# ADC.net
KiCad netlist of a schematic drawn in Altium Designer
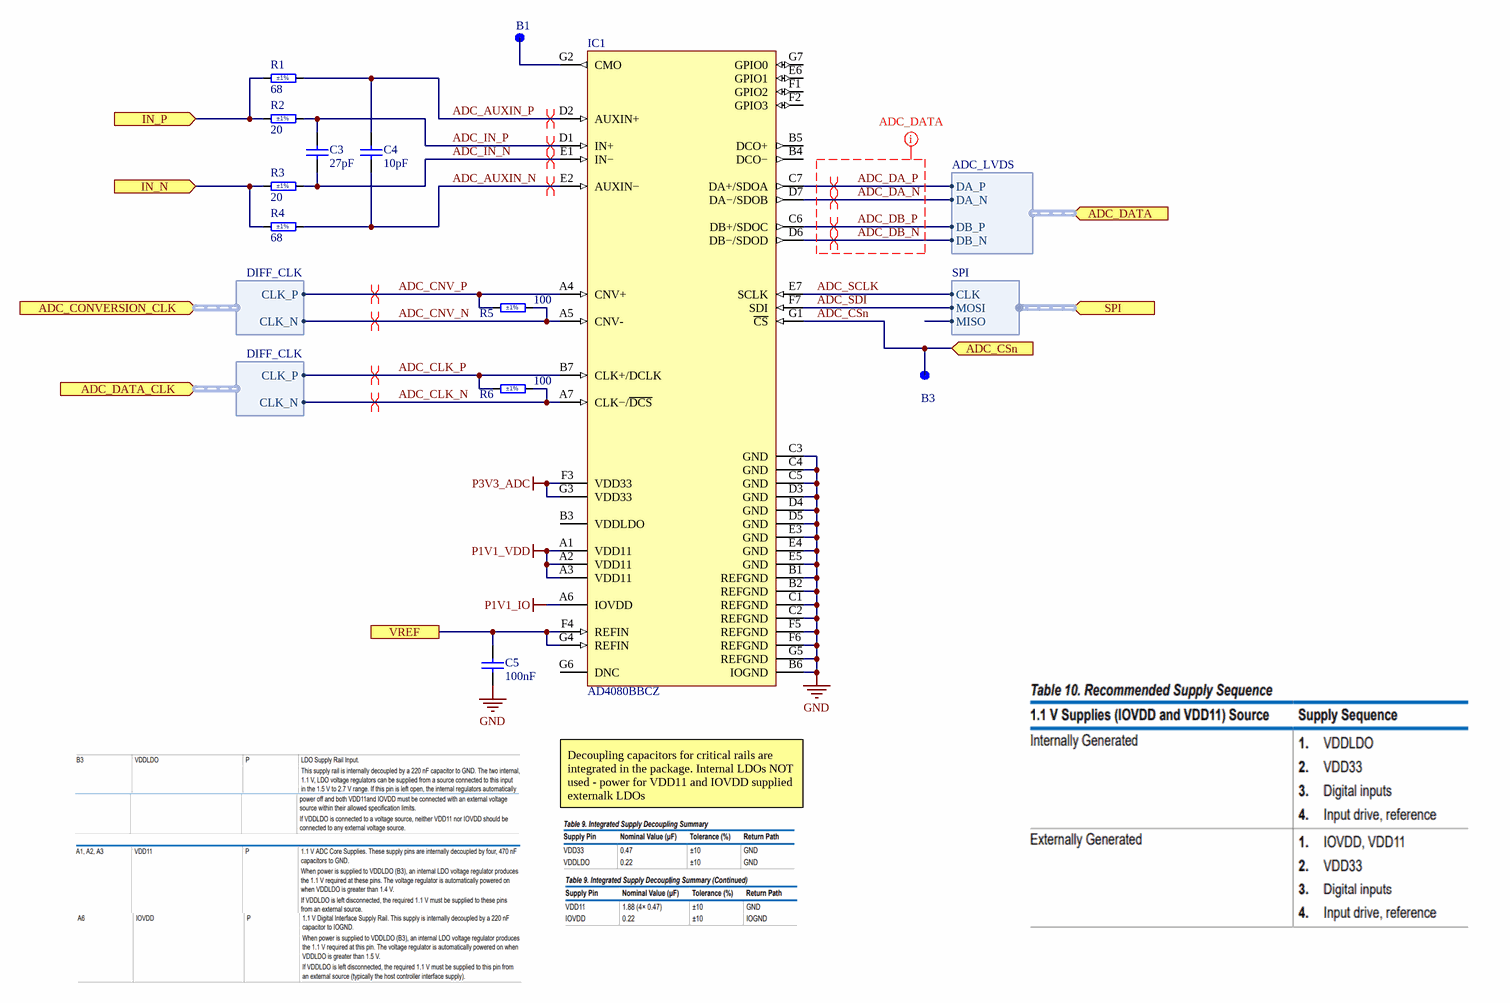
[diagram p0: ADC.SchDoc]

(export (version "E")
  (design (tool "Eeschema 10.0.6"))
  (components
    (comp (ref "B1")
      (value "SMD Pad")
      (footprint "C100")
      (description "Pad")
      (fields (field (name "PART NUMBER") "SMD_PAD_D1MM") (field (name "AUTHOR") "CERN DEM JLC"))
      (libsource (lib "Eletro-mechanical") (part "Single SMD Pad (Round)"))
    )
    (comp (ref "B3")
      (value "SMD Pad")
      (footprint "C100")
      (description "Pad")
      (fields (field (name "PART NUMBER") "SMD_PAD_D1MM") (field (name "AUTHOR") "CERN DEM JLC"))
      (libsource (lib "Eletro-mechanical") (part "Single SMD Pad (Round)"))
    )
    (comp (ref "C3")
      (value "27pF")
      (footprint "CAPC1005X55N")
      (description "Non-polarised capacitor")
      (fields
        (field (name "PART NUMBER") "CC0402_27PF_50V_5%_C0G")
        (field (name "VOLTAGE") "50V")
        (field (name "AUTHOR") "CERN DEM JLC")
      )
      (libsource (lib "Capacitors") (part "Capacitor - non polarized"))
    )
    (comp (ref "C4")
      (value "10pF")
      (footprint "CAPC1005X55N")
      (description "Non-polarised capacitor")
      (fields
        (field (name "PART NUMBER") "CC0402_10PF_50V_5%_C0G")
        (field (name "VOLTAGE") "50V")
        (field (name "AUTHOR") "CERN DEM JLC")
      )
      (libsource (lib "Capacitors") (part "Capacitor - non polarized"))
    )
    (comp (ref "C5")
      (value "100nF")
      (footprint "CAPC1005X55N")
      (description "Non-polarised capacitor")
      (fields
        (field (name "PART NUMBER") "CC0402_100NF_50V_10%_X7R")
        (field (name "VOLTAGE") "50V")
        (field (name "AUTHOR") "CERN DEM MR")
      )
      (libsource (lib "Capacitors") (part "Capacitor - non polarized"))
    )
    (comp (ref "IC1")
      (value "AD4080BBCZ")
      (footprint "BGA49C65P7X7_500X500X138")
      (description "20-Bit, 40 MSPS, Differential SAR ADC")
      (fields (field (name "MANUFACTURER") "Analog Devices") (field (name "AUTHOR") "Michal Beldyga"))
      (libsource (lib "Semiconductors") (part "AD4080"))
    )
    (comp (ref "R1")
      (value "68")
      (footprint "RESC1005X40N")
      (description "Resistor - 1%")
      (fields
        (field (name "TOLERANCE") "±1%")
        (field (name "PART NUMBER") "R0402_68R_1%_0.0625W_100PPM")
        (field (name "POWER") "0.0625W")
        (field (name "AUTHOR") "CERN DEM JLC")
      )
      (libsource (lib "Resistors") (part "Resistor - 1%"))
    )
    (comp (ref "R2")
      (value "20")
      (footprint "RESC1005X40N")
      (description "Resistor - 1%")
      (fields
        (field (name "TOLERANCE") "±1%")
        (field (name "PART NUMBER") "R0402_20R_1%_0.0625W_100PPM")
        (field (name "POWER") "0.0625W")
        (field (name "AUTHOR") "CERN DEM JLC")
      )
      (libsource (lib "Resistors") (part "Resistor - 1%"))
    )
    (comp (ref "R3")
      (value "20")
      (footprint "RESC1005X40N")
      (description "Resistor - 1%")
      (fields
        (field (name "TOLERANCE") "±1%")
        (field (name "PART NUMBER") "R0402_20R_1%_0.0625W_100PPM")
        (field (name "POWER") "0.0625W")
        (field (name "AUTHOR") "CERN DEM JLC")
      )
      (libsource (lib "Resistors") (part "Resistor - 1%"))
    )
    (comp (ref "R4")
      (value "68")
      (footprint "RESC1005X40N")
      (description "Resistor - 1%")
      (fields
        (field (name "TOLERANCE") "±1%")
        (field (name "PART NUMBER") "R0402_68R_1%_0.0625W_100PPM")
        (field (name "POWER") "0.0625W")
        (field (name "AUTHOR") "CERN DEM JLC")
      )
      (libsource (lib "Resistors") (part "Resistor - 1%"))
    )
    (comp (ref "R5")
      (value "100")
      (footprint "RESC1005X40N")
      (description "Resistor - 1%")
      (fields
        (field (name "TOLERANCE") "±1%")
        (field (name "PART NUMBER") "R0402_100R_1%_0.1W_100PPM")
        (field (name "POWER") "0.1W")
        (field (name "AUTHOR") "CERN DEM JLC")
      )
      (libsource (lib "Resistors") (part "Resistor - 1%"))
    )
    (comp (ref "R6")
      (value "100")
      (footprint "RESC1005X40N")
      (description "Resistor - 1%")
      (fields
        (field (name "TOLERANCE") "±1%")
        (field (name "PART NUMBER") "R0402_100R_1%_0.1W_100PPM")
        (field (name "POWER") "0.1W")
        (field (name "AUTHOR") "CERN DEM JLC")
      )
      (libsource (lib "Resistors") (part "Resistor - 1%"))
    )
  )
  (nets
    (net (code "4") (name "/ADC_AUXIN_N") (class "Default")
      (node (ref "C4") (pin "1") (pinfunction "1_1") (pintype "passive"))
      (node (ref "IC1") (pin "E2") (pinfunction "AUXIN−_E2") (pintype "input"))
      (node (ref "R4") (pin "2") (pinfunction "2_2") (pintype "passive"))
    )
    (net (code "5") (name "/ADC_AUXIN_P") (class "Default")
      (node (ref "C4") (pin "2") (pinfunction "2_2") (pintype "passive"))
      (node (ref "IC1") (pin "D2") (pinfunction "AUXIN+_D2") (pintype "input"))
      (node (ref "R1") (pin "2") (pinfunction "2_2") (pintype "passive"))
    )
    (net (code "6") (name "/ADC_CLK_N") (class "Default")
      (node (ref "IC1") (pin "A7") (pinfunction "CLK−/~{DCS}_A7") (pintype "input"))
      (node (ref "R6") (pin "2") (pinfunction "2_2") (pintype "passive"))
    )
    (net (code "7") (name "/ADC_CLK_P") (class "Default")
      (node (ref "IC1") (pin "B7") (pinfunction "CLK+/DCLK_B7") (pintype "input"))
      (node (ref "R6") (pin "1") (pinfunction "1_1") (pintype "passive"))
    )
    (net (code "8") (name "/ADC_CNV_N") (class "Default")
      (node (ref "IC1") (pin "A5") (pinfunction "CNV-_A5") (pintype "input"))
      (node (ref "R5") (pin "2") (pinfunction "2_2") (pintype "passive"))
    )
    (net (code "9") (name "/ADC_CNV_P") (class "Default")
      (node (ref "IC1") (pin "A4") (pinfunction "CNV+_A4") (pintype "input"))
      (node (ref "R5") (pin "1") (pinfunction "1_1") (pintype "passive"))
    )
    (net (code "10") (name "/ADC_CSn") (class "Default")
      (node (ref "B3") (pin "1") (pinfunction "1_1") (pintype "bidirectional"))
      (node (ref "IC1") (pin "G1") (pinfunction "~{CS}_G1") (pintype "input"))
    )
    (net (code "11") (name "/ADC_DA_N") (class "Default")
      (node (ref "IC1") (pin "D7") (pinfunction "DA−/SDOB_D7") (pintype "output"))
    )
    (net (code "12") (name "/ADC_DA_P") (class "Default")
      (node (ref "IC1") (pin "C7") (pinfunction "DA+/SDOA_C7") (pintype "output"))
    )
    (net (code "13") (name "/ADC_DB_N") (class "Default")
      (node (ref "IC1") (pin "D6") (pinfunction "DB−/SDOD_D6") (pintype "output"))
    )
    (net (code "14") (name "/ADC_DB_P") (class "Default")
      (node (ref "IC1") (pin "C6") (pinfunction "DB+/SDOC_C6") (pintype "output"))
    )
    (net (code "15") (name "/ADC_IN_N") (class "Default")
      (node (ref "C3") (pin "1") (pinfunction "1_1") (pintype "passive"))
      (node (ref "IC1") (pin "E1") (pinfunction "IN−_E1") (pintype "input"))
      (node (ref "R3") (pin "2") (pinfunction "2_2") (pintype "passive"))
    )
    (net (code "16") (name "/ADC_IN_P") (class "Default")
      (node (ref "C3") (pin "2") (pinfunction "2_2") (pintype "passive"))
      (node (ref "IC1") (pin "D1") (pinfunction "IN+_D1") (pintype "input"))
      (node (ref "R2") (pin "2") (pinfunction "2_2") (pintype "passive"))
    )
    (net (code "17") (name "/ADC_SCLK") (class "Default")
      (node (ref "IC1") (pin "E7") (pinfunction "SCLK_E7") (pintype "input"))
    )
    (net (code "18") (name "/ADC_SDI") (class "Default")
      (node (ref "IC1") (pin "F7") (pinfunction "SDI_F7") (pintype "input"))
    )
    (net (code "19") (name "/IN_N") (class "Default")
      (node (ref "R3") (pin "1") (pinfunction "1_1") (pintype "passive"))
      (node (ref "R4") (pin "1") (pinfunction "1_1") (pintype "passive"))
    )
    (net (code "20") (name "/IN_P") (class "Default")
      (node (ref "R1") (pin "1") (pinfunction "1_1") (pintype "passive"))
      (node (ref "R2") (pin "1") (pinfunction "1_1") (pintype "passive"))
    )
    (net (code "21") (name "/VREF") (class "Default")
      (node (ref "C5") (pin "2") (pinfunction "2_2") (pintype "passive"))
      (node (ref "IC1") (pin "F4") (pinfunction "REFIN_F4") (pintype "input"))
      (node (ref "IC1") (pin "G4") (pinfunction "REFIN_G4") (pintype "input"))
    )
    (net (code "25") (name "GND") (class "Default")
      (node (ref "C5") (pin "1") (pinfunction "1_1") (pintype "passive"))
      (node (ref "IC1") (pin "B1") (pinfunction "REFGND_B1") (pintype "power_in"))
      (node (ref "IC1") (pin "B2") (pinfunction "REFGND_B2") (pintype "power_in"))
      (node (ref "IC1") (pin "B6") (pinfunction "IOGND_B6") (pintype "power_in"))
      (node (ref "IC1") (pin "C1") (pinfunction "REFGND_C1") (pintype "power_in"))
      (node (ref "IC1") (pin "C2") (pinfunction "REFGND_C2") (pintype "power_in"))
      (node (ref "IC1") (pin "C3") (pinfunction "GND_C3") (pintype "power_in"))
      (node (ref "IC1") (pin "C4") (pinfunction "GND_C4") (pintype "power_in"))
      (node (ref "IC1") (pin "C5") (pinfunction "GND_C5") (pintype "power_in"))
      (node (ref "IC1") (pin "D3") (pinfunction "GND_D3") (pintype "power_in"))
      (node (ref "IC1") (pin "D4") (pinfunction "GND_D4") (pintype "power_in"))
      (node (ref "IC1") (pin "D5") (pinfunction "GND_D5") (pintype "power_in"))
      (node (ref "IC1") (pin "E3") (pinfunction "GND_E3") (pintype "power_in"))
      (node (ref "IC1") (pin "E4") (pinfunction "GND_E4") (pintype "power_in"))
      (node (ref "IC1") (pin "E5") (pinfunction "GND_E5") (pintype "power_in"))
      (node (ref "IC1") (pin "F5") (pinfunction "REFGND_F5") (pintype "power_in"))
      (node (ref "IC1") (pin "F6") (pinfunction "REFGND_F6") (pintype "power_in"))
      (node (ref "IC1") (pin "G5") (pinfunction "REFGND_G5") (pintype "power_in"))
    )
    (net (code "26") (name "Net-(IC1-CMO)") (class "Default")
      (node (ref "B1") (pin "1") (pinfunction "1_1") (pintype "bidirectional"))
      (node (ref "IC1") (pin "G2") (pinfunction "CMO_G2") (pintype "output"))
    )
    (net (code "27") (name "P1V1_IO") (class "Default")
      (node (ref "IC1") (pin "A6") (pinfunction "IOVDD_A6") (pintype "power_in"))
    )
    (net (code "28") (name "P1V1_VDD") (class "Default")
      (node (ref "IC1") (pin "A1") (pinfunction "VDD11_A1") (pintype "power_in"))
      (node (ref "IC1") (pin "A2") (pinfunction "VDD11_A2") (pintype "power_in"))
      (node (ref "IC1") (pin "A3") (pinfunction "VDD11_A3") (pintype "power_in"))
    )
    (net (code "29") (name "P3V3_ADC") (class "Default")
      (node (ref "IC1") (pin "F3") (pinfunction "VDD33_F3") (pintype "power_in"))
      (node (ref "IC1") (pin "G3") (pinfunction "VDD33_G3") (pintype "power_in"))
    )
    (net (code "30") (name "unconnected-(IC1-DCO+-PadB5)") (class "Default")
      (node (ref "IC1") (pin "B5") (pinfunction "DCO+_B5") (pintype "output"))
    )
    (net (code "31") (name "unconnected-(IC1-DCO−-PadB4)") (class "Default")
      (node (ref "IC1") (pin "B4") (pinfunction "DCO−_B4") (pintype "output"))
    )
    (net (code "32") (name "unconnected-(IC1-DNC-PadG6)") (class "Default")
      (node (ref "IC1") (pin "G6") (pinfunction "DNC_G6") (pintype "passive"))
    )
    (net (code "33") (name "unconnected-(IC1-GPIO0-PadG7)") (class "Default")
      (node (ref "IC1") (pin "G7") (pinfunction "GPIO0_G7") (pintype "bidirectional"))
    )
    (net (code "34") (name "unconnected-(IC1-GPIO1-PadE6)") (class "Default")
      (node (ref "IC1") (pin "E6") (pinfunction "GPIO1_E6") (pintype "bidirectional"))
    )
    (net (code "35") (name "unconnected-(IC1-GPIO2-PadF1)") (class "Default")
      (node (ref "IC1") (pin "F1") (pinfunction "GPIO2_F1") (pintype "bidirectional"))
    )
    (net (code "36") (name "unconnected-(IC1-GPIO3-PadF2)") (class "Default")
      (node (ref "IC1") (pin "F2") (pinfunction "GPIO3_F2") (pintype "bidirectional"))
    )
    (net (code "37") (name "unconnected-(IC1-VDDLDO-PadB3)") (class "Default")
      (node (ref "IC1") (pin "B3") (pinfunction "VDDLDO_B3") (pintype "power_in"))
    )
  )
)
